# BQ25756_Data_Config.net
KiCad netlist of a schematic drawn in Altium Designer
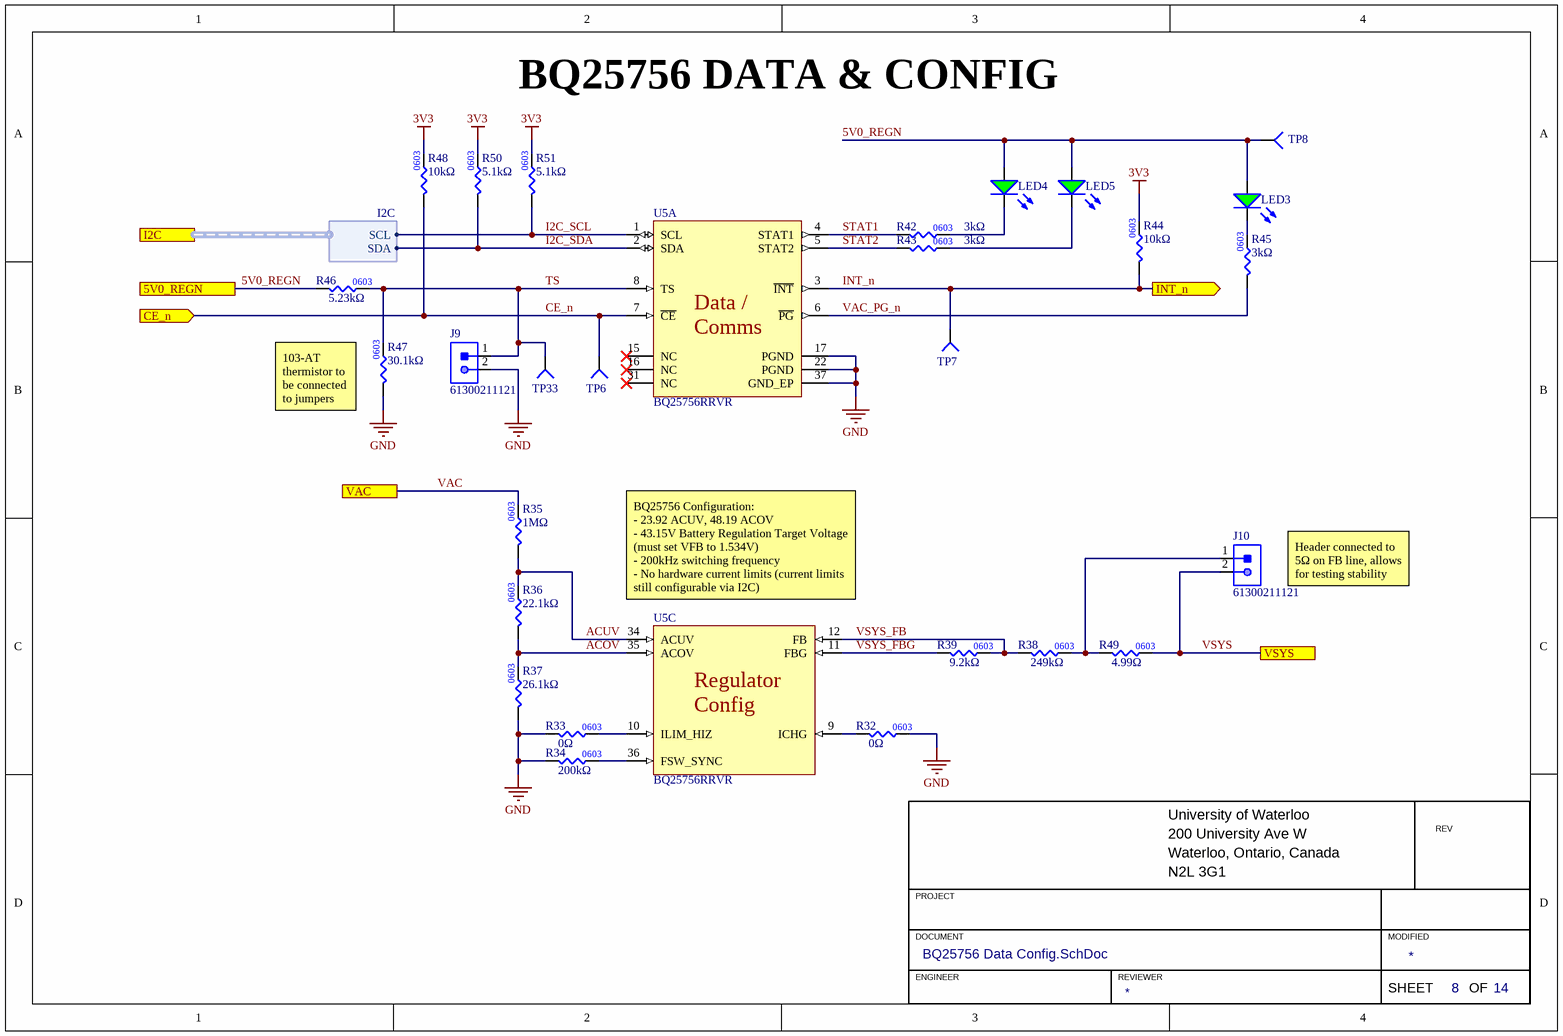
[diagram p0: BQ25756 Data Config.SchDoc]

(export (version "E")
  (design (tool "Eeschema 10.0.6"))
  (components
    (comp (ref "J9")
      (value "HEADER 2x1")
      (footprint "HDR1X2")
      (description "HEADER 2X1")
      (fields (field (name "MANUFACTURER PART NUMBER 1") "61300211121"))
      (libsource (lib "Personal_Schematic_Library_2022") (part "HEADER 2x1"))
    )
    (comp (ref "J10")
      (value "HEADER 2x1")
      (footprint "HDR1X2")
      (description "HEADER 2X1")
      (fields (field (name "MANUFACTURER PART NUMBER 1") "61300211121"))
      (libsource (lib "") (part "HEADER 2x1_1"))
    )
    (comp (ref "LED3")
      (value "LED_GREEN_0805")
      (footprint "LED_0805_GREEN")
      (description "LED GREEN DIFFUSED 0805 SMD")
      (libsource (lib "Personal_Schematic_Library_2022") (part "LED_GREEN_0805"))
    )
    (comp (ref "LED4")
      (value "LED_GREEN_0805")
      (footprint "LED_0805_GREEN")
      (description "LED GREEN DIFFUSED 0805 SMD")
      (libsource (lib "Personal_Schematic_Library_2022") (part "LED_GREEN_0805"))
    )
    (comp (ref "LED5")
      (value "LED_GREEN_0805")
      (footprint "LED_0805_GREEN")
      (description "LED GREEN DIFFUSED 0805 SMD")
      (libsource (lib "Personal_Schematic_Library_2022") (part "LED_GREEN_0805"))
    )
    (comp (ref "R32")
      (value "0Ω")
      (footprint "RES0603")
      (description "RES 0 OHM JUMPER 1/10W 0603")
      (fields (field (name "Comment") "RES_0Ω_0603"))
      (libsource (lib "Personal_Schematic_Library_2022") (part "RES_0Ω_0603"))
    )
    (comp (ref "R33")
      (value "0Ω")
      (footprint "RES0603")
      (description "RES 0 OHM JUMPER 1/10W 0603")
      (fields (field (name "Comment") "RES_0Ω_0603"))
      (libsource (lib "Personal_Schematic_Library_2022") (part "RES_0Ω_0603"))
    )
    (comp (ref "R34")
      (value "200kΩ")
      (footprint "RES0603")
      (description "RES 200K OHM 1% 1/10W 0603")
      (fields (field (name "Comment") "RES_200kΩ_0603_1%"))
      (libsource (lib "Personal_Schematic_Library_2022") (part "RES_200kΩ_0603_1%"))
    )
    (comp (ref "R35")
      (value "1MΩ")
      (footprint "RES0603")
      (description "RES 1M OHM 1% 1/10W 0603")
      (fields (field (name "Comment") "RES_1MΩ_0603_1%"))
      (libsource (lib "Personal_Schematic_Library_2022") (part "RES_1MΩ_0603_1%"))
    )
    (comp (ref "R36")
      (value "22.1kΩ")
      (footprint "RES0603")
      (description "RES 22.1K OHM 1% 1/10W 0603")
      (fields (field (name "Comment") "RES_22.1kΩ_0603_1%"))
      (libsource (lib "Personal_Schematic_Library_2022") (part "RES_22.1kΩ_0603_1%"))
    )
    (comp (ref "R37")
      (value "26.1kΩ")
      (footprint "RES0603")
      (description "RES 26.1K OHM 1% 1/10W 0603")
      (fields (field (name "Comment") "RES_26.1kΩ_0603_1%"))
      (libsource (lib "Personal_Schematic_Library_2022") (part "RES_26.1kΩ_0603_1%"))
    )
    (comp (ref "R38")
      (value "249kΩ")
      (footprint "RES0603")
      (description "RES 249K OHM 1% 1/10W 0603")
      (fields (field (name "Comment") "RES_249kΩ_0603_1%"))
      (libsource (lib "Personal_Schematic_Library_2022") (part "RES_249kΩ_0603_1%"))
    )
    (comp (ref "R39")
      (value "9.2kΩ")
      (footprint "RES0603")
      (description "RES 9.2K OHM 0.1% 1/10W 0603")
      (fields (field (name "Comment") "RES_9.2kΩ_0603_0.1%"))
      (libsource (lib "Personal_Schematic_Library_2022") (part "RES_9.2kΩ_0603_0.1%"))
    )
    (comp (ref "R42")
      (value "3kΩ")
      (footprint "RES0603")
      (description "RES 3K OHM 1% 1/10W 0603")
      (fields (field (name "Comment") "RES_3kΩ_0603_1%"))
      (libsource (lib "Personal_Schematic_Library_2022") (part "RES_3kΩ_0603_1%"))
    )
    (comp (ref "R43")
      (value "3kΩ")
      (footprint "RES0603")
      (description "RES 3K OHM 1% 1/10W 0603")
      (fields (field (name "Comment") "RES_3kΩ_0603_1%"))
      (libsource (lib "Personal_Schematic_Library_2022") (part "RES_3kΩ_0603_1%"))
    )
    (comp (ref "R44")
      (value "10kΩ")
      (footprint "RES0603")
      (description "RES 10K OHM 1% 1/8W 0603")
      (fields (field (name "Comment") "RES_10kΩ_0603_1%"))
      (libsource (lib "Personal_Schematic_Library_2022") (part "RES_10kΩ_0603_1%"))
    )
    (comp (ref "R45")
      (value "3kΩ")
      (footprint "RES0603")
      (description "RES 3K OHM 1% 1/10W 0603")
      (fields (field (name "Comment") "RES_3kΩ_0603_1%"))
      (libsource (lib "Personal_Schematic_Library_2022") (part "RES_3kΩ_0603_1%"))
    )
    (comp (ref "R46")
      (value "5.23kΩ")
      (footprint "RES0603")
      (description "RES SMD 5.23KOHM 0.1% 1/10W 0603")
      (fields (field (name "Comment") "RES_5.23kΩ_0603_0.1%"))
      (libsource (lib "Personal_Schematic_Library_2022") (part "RES_5.23kΩ_0603_0.1%"))
    )
    (comp (ref "R47")
      (value "30.1kΩ")
      (footprint "RES0603")
      (description "RES SMD 30.1KOHM 0.1% 1/10W 0603")
      (fields (field (name "Comment") "RES_30.1kΩ_0603_0.1%"))
      (libsource (lib "Personal_Schematic_Library_2022") (part "RES_30.1kΩ_0603_0.1%"))
    )
    (comp (ref "R48")
      (value "10kΩ")
      (footprint "RES0603")
      (description "RES 10K OHM 1% 1/8W 0603")
      (fields (field (name "Comment") "RES_10kΩ_0603_1%"))
      (libsource (lib "Personal_Schematic_Library_2022") (part "RES_10kΩ_0603_1%"))
    )
    (comp (ref "R49")
      (value "4.99Ω")
      (footprint "RES0603")
      (description "RES 4.99 OHM 1% 1/10W 0603")
      (fields (field (name "Comment") "RES_4.99Ω_0603_1%"))
      (libsource (lib "Personal_Schematic_Library_2022") (part "RES_4.99Ω_0603_1%"))
    )
    (comp (ref "R50")
      (value "5.1kΩ")
      (footprint "RES0603")
      (description "RES 5.1K OHM 1% 1/10W 0603")
      (fields (field (name "Comment") "RES_5.1kΩ_0603_1%"))
      (libsource (lib "Personal_Schematic_Library_2022") (part "RES_5.1kΩ_0603_1%"))
    )
    (comp (ref "R51")
      (value "5.1kΩ")
      (footprint "RES0603")
      (description "RES 5.1K OHM 1% 1/10W 0603")
      (fields (field (name "Comment") "RES_5.1kΩ_0603_1%"))
      (libsource (lib "Personal_Schematic_Library_2022") (part "RES_5.1kΩ_0603_1%"))
    )
    (comp (ref "TP6")
      (value "TESTPOINT_1MM_CIRCLE")
      (footprint "TESTPOINT_CIRCLE_1MM")
      (description "TESTPOINT 1MM CIRCLE")
      (libsource (lib "Personal_Schematic_Library_2022") (part "TESTPOINT_1MM_CIRCLE"))
    )
    (comp (ref "TP7")
      (value "TESTPOINT_1MM_CIRCLE")
      (footprint "TESTPOINT_CIRCLE_1MM")
      (description "TESTPOINT 1MM CIRCLE")
      (libsource (lib "Personal_Schematic_Library_2022") (part "TESTPOINT_1MM_CIRCLE"))
    )
    (comp (ref "TP8")
      (value "TESTPOINT_1MM_SQUARE")
      (footprint "TESTPOINT_SQUARE_1MM")
      (description "TESTPOINT 1MM SQUARE")
      (libsource (lib "Personal_Schematic_Library_2022") (part "TESTPOINT_1MM_SQUARE"))
    )
    (comp (ref "TP33")
      (value "TESTPOINT_1MM_CIRCLE")
      (footprint "TESTPOINT_CIRCLE_1MM")
      (description "TESTPOINT 1MM CIRCLE")
      (libsource (lib "Personal_Schematic_Library_2022") (part "TESTPOINT_1MM_CIRCLE"))
    )
    (comp (ref "U5")
      (value "BQ25756RRVR")
      (footprint "TI_36-VQFN")
      (description "IC BATT CHARGER BUCK-BOOST CTRLR")
      (libsource (lib "Personal_Schematic_Library_2022") (part "BQ25756RRVR"))
    )
  )
  (nets
    (net (code "2") (name "/5V0_REGN") (class "Default")
      (node (ref "LED3") (pin "1") (pinfunction "A_1") (pintype "passive"))
      (node (ref "LED4") (pin "1") (pinfunction "A_1") (pintype "passive"))
      (node (ref "LED5") (pin "1") (pinfunction "A_1") (pintype "passive"))
      (node (ref "R46") (pin "1") (pinfunction "1_1") (pintype "passive"))
      (node (ref "TP8") (pin "1") (pinfunction "=value_1") (pintype "passive"))
    )
    (net (code "3") (name "/ACOV") (class "Default")
      (node (ref "R36") (pin "1") (pinfunction "1_1") (pintype "passive"))
      (node (ref "R37") (pin "2") (pinfunction "2_2") (pintype "passive"))
      (node (ref "U5") (pin "35") (pinfunction "ACOV_35") (pintype "input"))
    )
    (net (code "4") (name "/ACUV") (class "Default")
      (node (ref "R35") (pin "1") (pinfunction "1_1") (pintype "passive"))
      (node (ref "R36") (pin "2") (pinfunction "2_2") (pintype "passive"))
      (node (ref "U5") (pin "34") (pinfunction "ACUV_34") (pintype "input"))
    )
    (net (code "5") (name "/CE_n") (class "Default")
      (node (ref "R48") (pin "1") (pinfunction "1_1") (pintype "passive"))
      (node (ref "TP6") (pin "1") (pinfunction "=value_1") (pintype "passive"))
      (node (ref "U5") (pin "7") (pinfunction "~{CE}_7") (pintype "input"))
    )
    (net (code "6") (name "/I2C_SCL") (class "Default")
      (node (ref "R51") (pin "1") (pinfunction "1_1") (pintype "passive"))
      (node (ref "U5") (pin "1") (pinfunction "SCL_1") (pintype "bidirectional"))
    )
    (net (code "7") (name "/I2C_SDA") (class "Default")
      (node (ref "R50") (pin "1") (pinfunction "1_1") (pintype "passive"))
      (node (ref "U5") (pin "2") (pinfunction "SDA_2") (pintype "bidirectional"))
    )
    (net (code "8") (name "/INT_n") (class "Default")
      (node (ref "R44") (pin "1") (pinfunction "1_1") (pintype "passive"))
      (node (ref "TP7") (pin "1") (pinfunction "=value_1") (pintype "passive"))
      (node (ref "U5") (pin "3") (pinfunction "~{INT}_3") (pintype "output"))
    )
    (net (code "9") (name "/STAT1") (class "Default")
      (node (ref "R42") (pin "1") (pinfunction "1_1") (pintype "passive"))
      (node (ref "U5") (pin "4") (pinfunction "STAT1_4") (pintype "output"))
    )
    (net (code "10") (name "/STAT2") (class "Default")
      (node (ref "R43") (pin "1") (pinfunction "1_1") (pintype "passive"))
      (node (ref "U5") (pin "5") (pinfunction "STAT2_5") (pintype "output"))
    )
    (net (code "11") (name "/TS") (class "Default")
      (node (ref "J9") (pin "1") (pinfunction "VCC_1") (pintype "passive"))
      (node (ref "R46") (pin "2") (pinfunction "2_2") (pintype "passive"))
      (node (ref "R47") (pin "2") (pinfunction "2_2") (pintype "passive"))
      (node (ref "TP33") (pin "1") (pinfunction "=value_1") (pintype "passive"))
      (node (ref "U5") (pin "8") (pinfunction "TS_8") (pintype "input"))
    )
    (net (code "12") (name "/VAC") (class "Default")
      (node (ref "R35") (pin "2") (pinfunction "2_2") (pintype "passive"))
    )
    (net (code "13") (name "/VAC_PG_n") (class "Default")
      (node (ref "R45") (pin "1") (pinfunction "1_1") (pintype "passive"))
      (node (ref "U5") (pin "6") (pinfunction "~{PG}_6") (pintype "output"))
    )
    (net (code "14") (name "/VSYS") (class "Default")
      (node (ref "J10") (pin "2") (pinfunction "2_2") (pintype "passive"))
      (node (ref "R49") (pin "2") (pinfunction "2_2") (pintype "passive"))
    )
    (net (code "15") (name "/VSYS_FB") (class "Default")
      (node (ref "R38") (pin "1") (pinfunction "1_1") (pintype "passive"))
      (node (ref "R39") (pin "2") (pinfunction "2_2") (pintype "passive"))
      (node (ref "U5") (pin "12") (pinfunction "FB_12") (pintype "input"))
    )
    (net (code "16") (name "/VSYS_FBG") (class "Default")
      (node (ref "R39") (pin "1") (pinfunction "1_1") (pintype "passive"))
      (node (ref "U5") (pin "11") (pinfunction "FBG_11") (pintype "input"))
    )
    (net (code "18") (name "3V3") (class "Default")
      (node (ref "R44") (pin "2") (pinfunction "2_2") (pintype "passive"))
      (node (ref "R48") (pin "2") (pinfunction "2_2") (pintype "passive"))
      (node (ref "R50") (pin "2") (pinfunction "2_2") (pintype "passive"))
      (node (ref "R51") (pin "2") (pinfunction "2_2") (pintype "passive"))
    )
    (net (code "19") (name "GND") (class "Default")
      (node (ref "J9") (pin "2") (pinfunction "2_2") (pintype "passive"))
      (node (ref "R32") (pin "2") (pinfunction "2_2") (pintype "passive"))
      (node (ref "R33") (pin "1") (pinfunction "1_1") (pintype "passive"))
      (node (ref "R34") (pin "1") (pinfunction "1_1") (pintype "passive"))
      (node (ref "R37") (pin "1") (pinfunction "1_1") (pintype "passive"))
      (node (ref "R47") (pin "1") (pinfunction "1_1") (pintype "passive"))
      (node (ref "U5") (pin "17") (pinfunction "PGND_17") (pintype "power_in"))
      (node (ref "U5") (pin "22") (pinfunction "PGND_22") (pintype "power_in"))
      (node (ref "U5") (pin "37") (pinfunction "GND_EP_37") (pintype "power_in"))
    )
    (net (code "20") (name "Net-(J10-VCC)") (class "Default")
      (node (ref "J10") (pin "1") (pinfunction "VCC_1") (pintype "passive"))
      (node (ref "R38") (pin "2") (pinfunction "2_2") (pintype "passive"))
      (node (ref "R49") (pin "1") (pinfunction "1_1") (pintype "passive"))
    )
    (net (code "21") (name "Net-(LED3-K)") (class "Default")
      (node (ref "LED3") (pin "2") (pinfunction "K_2") (pintype "passive"))
      (node (ref "R45") (pin "2") (pinfunction "2_2") (pintype "passive"))
    )
    (net (code "22") (name "Net-(LED4-K)") (class "Default")
      (node (ref "LED4") (pin "2") (pinfunction "K_2") (pintype "passive"))
      (node (ref "R42") (pin "2") (pinfunction "2_2") (pintype "passive"))
    )
    (net (code "23") (name "Net-(LED5-K)") (class "Default")
      (node (ref "LED5") (pin "2") (pinfunction "K_2") (pintype "passive"))
      (node (ref "R43") (pin "2") (pinfunction "2_2") (pintype "passive"))
    )
    (net (code "24") (name "Net-(U5C-FSW_SYNC)") (class "Default")
      (node (ref "R34") (pin "2") (pinfunction "2_2") (pintype "passive"))
      (node (ref "U5") (pin "36") (pinfunction "FSW_SYNC_36") (pintype "input"))
    )
    (net (code "25") (name "Net-(U5C-ICHG)") (class "Default")
      (node (ref "R32") (pin "1") (pinfunction "1_1") (pintype "passive"))
      (node (ref "U5") (pin "9") (pinfunction "ICHG_9") (pintype "input"))
    )
    (net (code "26") (name "Net-(U5C-ILIM_HIZ)") (class "Default")
      (node (ref "R33") (pin "2") (pinfunction "2_2") (pintype "passive"))
      (node (ref "U5") (pin "10") (pinfunction "ILIM_HIZ_10") (pintype "input"))
    )
    (net (code "27") (name "unconnected-(U5A-NC-Pad15)") (class "Default")
      (node (ref "U5") (pin "15") (pinfunction "NC_15") (pintype "passive+no_connect"))
    )
    (net (code "28") (name "unconnected-(U5A-NC-Pad16)") (class "Default")
      (node (ref "U5") (pin "16") (pinfunction "NC_16") (pintype "passive+no_connect"))
    )
    (net (code "29") (name "unconnected-(U5A-NC-Pad31)") (class "Default")
      (node (ref "U5") (pin "31") (pinfunction "NC_31") (pintype "passive+no_connect"))
    )
  )
)
